# debugging_board_3_KEY2.net
KiCad netlist of a schematic drawn in Altium Designer
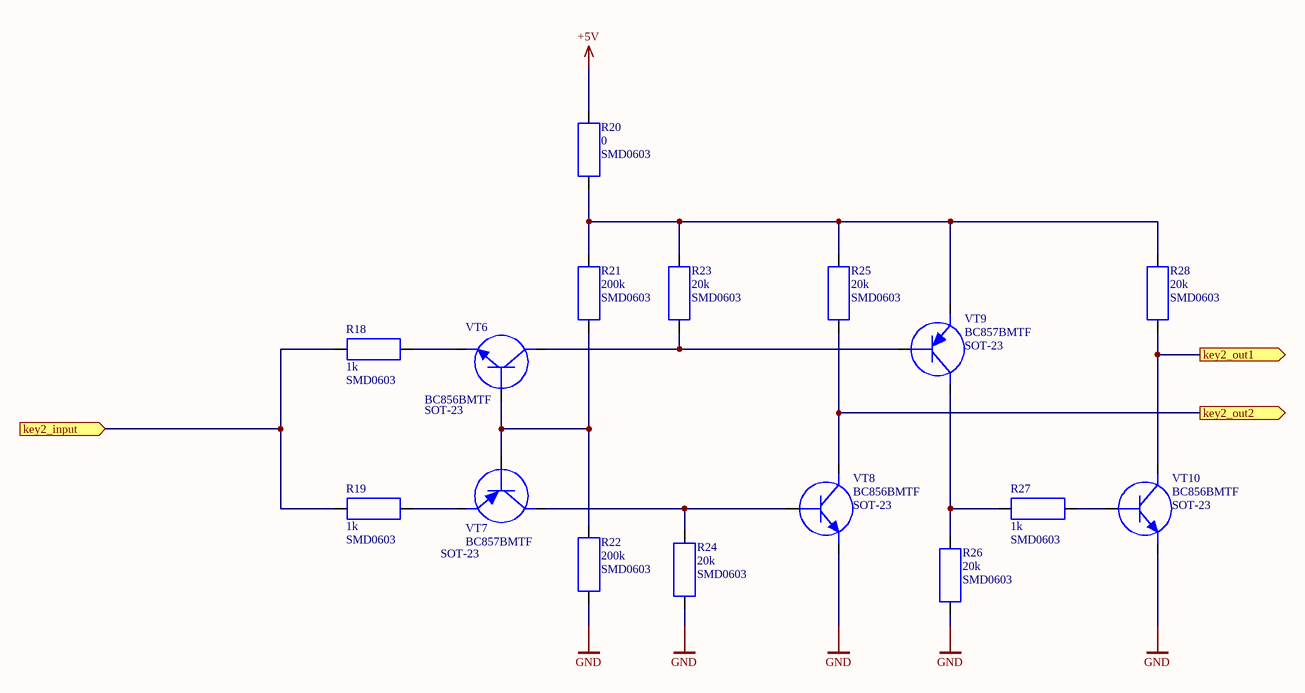
[diagram p0: debugging_board_3_KEY2.SchDoc]

(export (version "E")
  (design (tool "Eeschema 10.0.6"))
  (components
    (comp (ref "R18")
      (value "1k")
      (footprint "SMD0603(1005)")
      (fields (field (name "PACKAGE") "SMD0603"))
      (libsource (lib "MechanikLibrary") (part "R_0603"))
    )
    (comp (ref "R19")
      (value "1k")
      (footprint "SMD0603(1005)")
      (fields (field (name "PACKAGE") "SMD0603"))
      (libsource (lib "MechanikLibrary") (part "R_0603"))
    )
    (comp (ref "R20")
      (value "0")
      (footprint "SMD0603(1005)")
      (fields (field (name "PACKAGE") "SMD0603"))
      (libsource (lib "MechanikLibrary") (part "R_0603"))
    )
    (comp (ref "R21")
      (value "200k")
      (footprint "SMD0603(1005)")
      (fields (field (name "PACKAGE") "SMD0603"))
      (libsource (lib "MechanikLibrary") (part "R_0603"))
    )
    (comp (ref "R22")
      (value "200k")
      (footprint "SMD0603(1005)")
      (fields (field (name "PACKAGE") "SMD0603"))
      (libsource (lib "MechanikLibrary") (part "R_0603"))
    )
    (comp (ref "R23")
      (value "20k")
      (footprint "SMD0603(1005)")
      (fields (field (name "PACKAGE") "SMD0603"))
      (libsource (lib "MechanikLibrary") (part "R_0603"))
    )
    (comp (ref "R24")
      (value "20k")
      (footprint "SMD0603(1005)")
      (fields (field (name "PACKAGE") "SMD0603"))
      (libsource (lib "MechanikLibrary") (part "R_0603"))
    )
    (comp (ref "R25")
      (value "20k")
      (footprint "SMD0603(1005)")
      (fields (field (name "PACKAGE") "SMD0603"))
      (libsource (lib "MechanikLibrary") (part "R_0603"))
    )
    (comp (ref "R26")
      (value "20k")
      (footprint "SMD0603(1005)")
      (fields (field (name "PACKAGE") "SMD0603"))
      (libsource (lib "MechanikLibrary") (part "R_0603"))
    )
    (comp (ref "R27")
      (value "1k")
      (footprint "SMD0603(1005)")
      (fields (field (name "PACKAGE") "SMD0603"))
      (libsource (lib "MechanikLibrary") (part "R_0603"))
    )
    (comp (ref "R28")
      (value "20k")
      (footprint "SMD0603(1005)")
      (fields (field (name "PACKAGE") "SMD0603"))
      (libsource (lib "MechanikLibrary") (part "R_0603"))
    )
    (comp (ref "VT6")
      (value "BC856BMTF")
      (footprint "SOT23-3")
      (fields (field (name "PACKAGE") "SOT-23"))
      (libsource (lib "MechanikLibrary") (part "VT_NPN_SOT23_3"))
    )
    (comp (ref "VT7")
      (value "BC857BMTF")
      (footprint "SOT23-3")
      (fields (field (name "PACKAGE") "SOT-23"))
      (libsource (lib "MechanikLibrary") (part "VT_PNP_SOT23_3"))
    )
    (comp (ref "VT8")
      (value "BC856BMTF")
      (footprint "SOT23-3")
      (fields (field (name "PACKAGE") "SOT-23"))
      (libsource (lib "MechanikLibrary") (part "VT_NPN_SOT23_3"))
    )
    (comp (ref "VT9")
      (value "BC857BMTF")
      (footprint "SOT23-3")
      (fields (field (name "PACKAGE") "SOT-23"))
      (libsource (lib "MechanikLibrary") (part "VT_PNP_SOT23_3"))
    )
    (comp (ref "VT10")
      (value "BC856BMTF")
      (footprint "SOT23-3")
      (fields (field (name "PACKAGE") "SOT-23"))
      (libsource (lib "MechanikLibrary") (part "VT_NPN_SOT23_3"))
    )
  )
  (nets
    (net (code "1") (name "+5V") (class "Default") (node (ref "R20") (pin "1") (pintype "passive")))
    (net (code "2") (name "/key2_input") (class "Default")
      (node (ref "R18") (pin "2") (pintype "passive"))
      (node (ref "R19") (pin "2") (pintype "passive"))
    )
    (net (code "3") (name "/key2_out1") (class "Default")
      (node (ref "R28") (pin "2") (pintype "passive"))
      (node (ref "VT10") (pin "3") (pintype "passive"))
    )
    (net (code "4") (name "/key2_out2") (class "Default")
      (node (ref "R25") (pin "2") (pintype "passive"))
      (node (ref "VT8") (pin "3") (pintype "passive"))
    )
    (net (code "5") (name "GND") (class "Default")
      (node (ref "R22") (pin "2") (pintype "passive"))
      (node (ref "R24") (pin "2") (pintype "passive"))
      (node (ref "R26") (pin "2") (pintype "passive"))
      (node (ref "VT10") (pin "2") (pintype "passive"))
      (node (ref "VT8") (pin "2") (pintype "passive"))
    )
    (net (code "6") (name "Net-(R18-Pad1)") (class "Default")
      (node (ref "R18") (pin "1") (pintype "passive"))
      (node (ref "VT6") (pin "2") (pintype "passive"))
    )
    (net (code "7") (name "Net-(R19-Pad1)") (class "Default")
      (node (ref "R19") (pin "1") (pintype "passive"))
      (node (ref "VT7") (pin "2") (pintype "passive"))
    )
    (net (code "8") (name "Net-(R20-Pad2)") (class "Default")
      (node (ref "R20") (pin "2") (pintype "passive"))
      (node (ref "R21") (pin "1") (pintype "passive"))
      (node (ref "R23") (pin "1") (pintype "passive"))
      (node (ref "R25") (pin "1") (pintype "passive"))
      (node (ref "R28") (pin "1") (pintype "passive"))
      (node (ref "VT9") (pin "2") (pintype "passive"))
    )
    (net (code "9") (name "Net-(R21-Pad2)") (class "Default")
      (node (ref "R21") (pin "2") (pintype "passive"))
      (node (ref "R22") (pin "1") (pintype "passive"))
      (node (ref "VT6") (pin "1") (pintype "passive"))
      (node (ref "VT7") (pin "1") (pintype "passive"))
    )
    (net (code "10") (name "Net-(R23-Pad2)") (class "Default")
      (node (ref "R23") (pin "2") (pintype "passive"))
      (node (ref "VT6") (pin "3") (pintype "passive"))
      (node (ref "VT9") (pin "1") (pintype "passive"))
    )
    (net (code "11") (name "Net-(R24-Pad1)") (class "Default")
      (node (ref "R24") (pin "1") (pintype "passive"))
      (node (ref "VT7") (pin "3") (pintype "passive"))
      (node (ref "VT8") (pin "1") (pintype "passive"))
    )
    (net (code "12") (name "Net-(R26-Pad1)") (class "Default")
      (node (ref "R26") (pin "1") (pintype "passive"))
      (node (ref "R27") (pin "2") (pintype "passive"))
      (node (ref "VT9") (pin "3") (pintype "passive"))
    )
    (net (code "13") (name "Net-(R27-Pad1)") (class "Default")
      (node (ref "R27") (pin "1") (pintype "passive"))
      (node (ref "VT10") (pin "1") (pintype "passive"))
    )
  )
)
